# power.net
KiCad netlist of a schematic drawn in Altium Designer
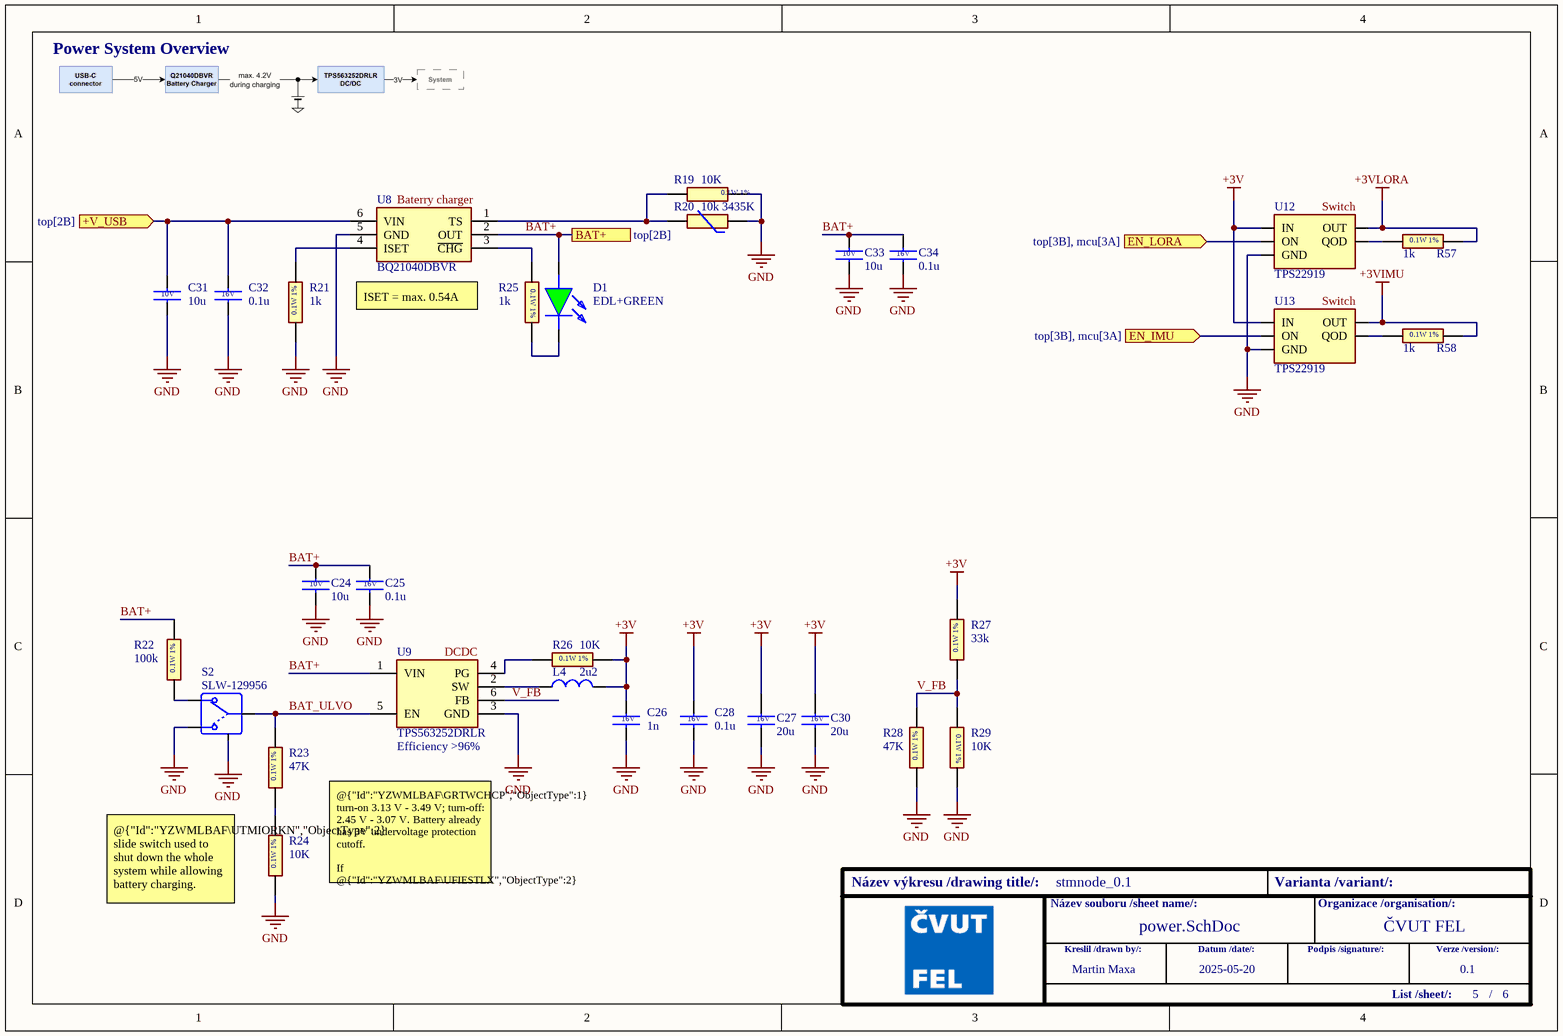
[diagram p0: power.SchDoc]

(export (version "E")
  (design (tool "Eeschema 10.0.6"))
  (components
    (comp (ref "C24")
      (value "10u")
      (footprint "C0603")
      (description "10 VDC, 20 %, X5R")
      (fields
        (field (name "MANUFACTURER_PART_NUMBER") "C0603C106M8PACTU")
        (field (name "MOUSER PART NUMBER") "80-C0603C106M8PACTU")
      )
      (libsource (lib "bch-lib") (part "ECK+10u10V"))
    )
    (comp (ref "C25")
      (value "0.1u")
      (footprint "CAPC1608X95N")
      (description "16V 0.1uF XR7 0603 10%")
      (fields
        (field (name "MANUFACTURER_PART_NUMBER") "C0603C104K4RAC-TU")
        (field (name "MOUSER PART NUMBER") "80-C0603C104K4RAC")
      )
      (libsource (lib "bch-lib") (part "ECK+100n16V"))
    )
    (comp (ref "C26")
      (value "1n")
      (footprint "CAPC1608X87N")
      (description "16 VDC, 10 %, X7R")
      (fields (field (name "MANUFACTURER_PART_NUMBER") "C0603C102K4RECTU"))
      (libsource (lib "bch-lib") (part "ECK+1n16V"))
    )
    (comp (ref "C27")
      (value "20u")
      (footprint "C0603")
      (description "Capacitor")
      (fields
        (field (name "MANUFACTURER_PART_NUMBER") "C0603C200K4HACAUTO")
        (field (name "MOUSER PART NUMBER") "80-C0603C200K4HAUTO")
      )
      (libsource (lib "bch-lib") (part "ECK+20u16V"))
    )
    (comp (ref "C28")
      (value "0.1u")
      (footprint "CAPC1608X95N")
      (description "16V 0.1uF XR7 0603 10%")
      (fields
        (field (name "MANUFACTURER_PART_NUMBER") "C0603C104K4RAC-TU")
        (field (name "MOUSER PART NUMBER") "80-C0603C104K4RAC")
      )
      (libsource (lib "bch-lib") (part "ECK+100n16V"))
    )
    (comp (ref "C30")
      (value "20u")
      (footprint "C0603")
      (description "Capacitor")
      (fields
        (field (name "MANUFACTURER_PART_NUMBER") "C0603C200K4HACAUTO")
        (field (name "MOUSER PART NUMBER") "80-C0603C200K4HAUTO")
      )
      (libsource (lib "bch-lib") (part "ECK+20u16V"))
    )
    (comp (ref "C31")
      (value "10u")
      (footprint "C0603")
      (description "10 VDC, 20 %, X5R")
      (fields
        (field (name "MANUFACTURER_PART_NUMBER") "C0603C106M8PACTU")
        (field (name "MOUSER PART NUMBER") "80-C0603C106M8PACTU")
      )
      (libsource (lib "bch-lib") (part "ECK+10u10V"))
    )
    (comp (ref "C32")
      (value "0.1u")
      (footprint "CAPC1608X95N")
      (description "16V 0.1uF XR7 0603 10%")
      (fields
        (field (name "MANUFACTURER_PART_NUMBER") "C0603C104K4RAC-TU")
        (field (name "MOUSER PART NUMBER") "80-C0603C104K4RAC")
      )
      (libsource (lib "bch-lib") (part "ECK+100n16V"))
    )
    (comp (ref "C33")
      (value "10u")
      (footprint "C0603")
      (description "10 VDC, 20 %, X5R")
      (fields
        (field (name "MANUFACTURER_PART_NUMBER") "C0603C106M8PACTU")
        (field (name "MOUSER PART NUMBER") "80-C0603C106M8PACTU")
      )
      (libsource (lib "bch-lib") (part "ECK+10u10V"))
    )
    (comp (ref "C34")
      (value "0.1u")
      (footprint "CAPC1608X95N")
      (description "16V 0.1uF XR7 0603 10%")
      (fields
        (field (name "MANUFACTURER_PART_NUMBER") "C0603C104K4RAC-TU")
        (field (name "MOUSER PART NUMBER") "80-C0603C104K4RAC")
      )
      (libsource (lib "bch-lib") (part "ECK+100n16V"))
    )
    (comp (ref "D1")
      (value "EDL+GREEN")
      (footprint "LEDM2012X80N")
      (description "LED GREEN,  3.2 V")
      (fields
        (field (name "MANUFACTURER_PART_NUMBER") "150080GS75000")
        (field (name "MOUSER PART NUMBER") "710-150080GS75000")
      )
      (libsource (lib "bch-lib") (part "EDL+GREEN"))
    )
    (comp (ref "L4")
      (value "2u2")
      (footprint "INDPM5752X300N")
      (description "Power Inductors - SMD 2.2uH 20%")
      (fields
        (field (name "MANUFACTURER_PART_NUMBER") "SRP5030TA-2R2M")
        (field (name "MOUSER PART NUMBER") "652-SRP5030TA-2R2M")
      )
      (libsource (lib "bch-lib") (part "EL+2.2u5.5A"))
    )
    (comp (ref "R19")
      (value "10K")
      (footprint "RESC1608X50N")
      (description "Resistor 1%, 0.1W")
      (fields
        (field (name "MANUFACTURER_PART_NUMBER") "CRCW060310K0FKEA")
        (field (name "MOUSER PART NUMBER") "71-CRCW0603-10K-E3")
      )
      (libsource (lib "") (part "ER+10K_1"))
    )
    (comp (ref "R20")
      (value "10k 3435K")
      (footprint "THRMC1608X90N")
      (description "NTC (Negative Temperature Coefficient) Thermistors NTC,10K,1%,0603,125C,AEC-Q200,ECO")
      (fields
        (field (name "MANUFACTURER_PART_NUMBER") "NTCGS163JF103FT7")
        (field (name "MOUSER PART NUMBER") "810-NTCGS163JF103FT7")
      )
      (libsource (lib "bch-lib") (part "ER+10kNTC3435K"))
    )
    (comp (ref "R21")
      (value "1k")
      (footprint "RESC1608X50N")
      (description "Resistor 1%, 0.1W")
      (fields
        (field (name "MANUFACTURER_PART_NUMBER") "CRCW06031K00FKEA")
        (field (name "MOUSER PART NUMBER") "71-CRCW0603-1.0K-E3")
      )
      (libsource (lib "") (part "ER+1K_1"))
    )
    (comp (ref "R22")
      (value "100k")
      (footprint "RESC1608X55N")
      (description "Thick Film Resistors 0603 - SMD 1/10Watt 100Kohms 1% Commercial Use")
      (fields
        (field (name "MANUFACTURER_PART_NUMBER") "AC0603FR-10100KL")
        (field (name "MOUSER PART NUMBER") "603-AC0603FR-10100KL")
      )
      (libsource (lib "bch-lib") (part "ER+100k"))
    )
    (comp (ref "R23")
      (value "47K")
      (footprint "RESC1608X50N")
      (description "Resistor 1%, 0.1W")
      (fields
        (field (name "MANUFACTURER_PART_NUMBER") "CRCW060347K0FKEA")
        (field (name "MOUSER PART NUMBER") "71-CRCW0603-47K-E3")
      )
      (libsource (lib "bch-lib") (part "ER+47K"))
    )
    (comp (ref "R24")
      (value "10K")
      (footprint "RESC1608X50N")
      (description "Resistor 1%, 0.1W")
      (fields
        (field (name "MANUFACTURER_PART_NUMBER") "CRCW060310K0FKEA")
        (field (name "MOUSER PART NUMBER") "71-CRCW0603-10K-E3")
      )
      (libsource (lib "") (part "ER+10K_2"))
    )
    (comp (ref "R25")
      (value "1k")
      (footprint "RESC1608X50N")
      (description "Resistor 1%, 0.1W")
      (fields
        (field (name "MANUFACTURER_PART_NUMBER") "CRCW06031K00FKEA")
        (field (name "MOUSER PART NUMBER") "71-CRCW0603-1.0K-E3")
      )
      (libsource (lib "") (part "ER+1K_2"))
    )
    (comp (ref "R26")
      (value "10K")
      (footprint "RESC1608X50N")
      (description "Resistor 1%, 0.1W")
      (fields
        (field (name "MANUFACTURER_PART_NUMBER") "CRCW060310K0FKEA")
        (field (name "MOUSER PART NUMBER") "71-CRCW0603-10K-E3")
      )
      (libsource (lib "bch-lib") (part "ER+10K"))
    )
    (comp (ref "R27")
      (value "33k")
      (footprint "RESC1608X55N")
      (description "Thick Film Resistors - SMD General Purpose Chip Resistor 0603, 33kOhms, 1%, 1/10W")
      (fields
        (field (name "MANUFACTURER_PART_NUMBER") "RC0603FR-1333KL")
        (field (name "MOUSER PART NUMBER") "603-RC0603FR-1333KL")
      )
      (libsource (lib "bch-lib") (part "ER+33k"))
    )
    (comp (ref "R28")
      (value "47K")
      (footprint "RESC1608X50N")
      (description "Resistor 1%, 0.1W")
      (fields
        (field (name "MANUFACTURER_PART_NUMBER") "CRCW060347K0FKEA")
        (field (name "MOUSER PART NUMBER") "71-CRCW0603-47K-E3")
      )
      (libsource (lib "bch-lib") (part "ER+47K"))
    )
    (comp (ref "R29")
      (value "10K")
      (footprint "RESC1608X50N")
      (description "Resistor 1%, 0.1W")
      (fields
        (field (name "MANUFACTURER_PART_NUMBER") "CRCW060310K0FKEA")
        (field (name "MOUSER PART NUMBER") "71-CRCW0603-10K-E3")
      )
      (libsource (lib "") (part "ER+10K_1"))
    )
    (comp (ref "R57")
      (value "1k")
      (footprint "RESC1608X50N")
      (description "Resistor 1%, 0.1W")
      (fields
        (field (name "MANUFACTURER_PART_NUMBER") "CRCW06031K00FKEA")
        (field (name "MOUSER PART NUMBER") "71-CRCW0603-1.0K-E3")
      )
      (libsource (lib "bch-lib") (part "ER+1K"))
    )
    (comp (ref "R58")
      (value "1k")
      (footprint "RESC1608X50N")
      (description "Resistor 1%, 0.1W")
      (fields
        (field (name "MANUFACTURER_PART_NUMBER") "CRCW06031K00FKEA")
        (field (name "MOUSER PART NUMBER") "71-CRCW0603-1.0K-E3")
      )
      (libsource (lib "bch-lib") (part "ER+1K"))
    )
    (comp (ref "S2")
      (value "SLW-129956")
      (footprint "SLW1299564ARAND")
      (description "Slide Switch, Right Angle, max. 50 VDC, max. 300 mA, ON - ON")
      (fields
        (field (name "MANUFACTURER_PART_NUMBER") "SLW-129956-4A-RA-N-D")
        (field (name "MOUSER PART NUMBER") "179-SLW1299564ARAND")
      )
      (libsource (lib "bch-lib") (part "ESW-SLW-129956"))
    )
    (comp (ref "U8")
      (value "BQ21040DBVR")
      (footprint "SOT95P280X145-6N")
      (description "Battery Management 1-cell 0.8-A Li-ion and Li-polymer batt A 595-BQ21040DBVT")
      (fields (field (name "MOUSER PART NUMBER") "595-BQ21040DBVR"))
      (libsource (lib "bch-lib") (part "EU+BQ21040DBVR"))
    )
    (comp (ref "U9")
      (value "TPS563252DRLR")
      (footprint "SOTFL50P160X60-6N")
      (description "Switching Voltage Regulators 3-V to 17-V input vo ltage 3-A 1.2-Mhz")
      (fields (field (name "MOUSER PART NUMBER") "595-TPS563252DRLR"))
      (libsource (lib "bch-lib") (part "EU+TPS563252DRLR"))
    )
    (comp (ref "U12")
      (value "TPS22919")
      (footprint "SOT65P210X110-6N")
      (description "Power Switch ICs - Power Distribution 1-ch 5.5V 1.5A 90 mOhm self-protected AE")
      (fields
        (field (name "MANUFACTURER_PART_NUMBER") "TPS22919QDCKRQ1")
        (field (name "MOUSER PART NUMBER") "595-TPS22919QDCKRQ1")
      )
      (libsource (lib "bch-lib") (part "EU+TPS22919"))
    )
    (comp (ref "U13")
      (value "TPS22919")
      (footprint "SOT65P210X110-6N")
      (description "Power Switch ICs - Power Distribution 1-ch 5.5V 1.5A 90 mOhm self-protected AE")
      (fields
        (field (name "MANUFACTURER_PART_NUMBER") "TPS22919QDCKRQ1")
        (field (name "MOUSER PART NUMBER") "595-TPS22919QDCKRQ1")
      )
      (libsource (lib "bch-lib") (part "EU+TPS22919"))
    )
  )
  (nets
    (net (code "1") (name "+3V") (class "Default")
      (node (ref "C26") (pin "1") (pinfunction "1_1") (pintype "passive"))
      (node (ref "C27") (pin "1") (pinfunction "1_1") (pintype "passive"))
      (node (ref "C28") (pin "1") (pinfunction "1_1") (pintype "passive"))
      (node (ref "C30") (pin "1") (pinfunction "1_1") (pintype "passive"))
      (node (ref "L4") (pin "24") (pinfunction "24_24") (pintype "passive"))
      (node (ref "R26") (pin "2") (pinfunction "2_2") (pintype "passive"))
      (node (ref "R27") (pin "2") (pinfunction "2_2") (pintype "passive"))
      (node (ref "U12") (pin "1") (pinfunction "IN_1") (pintype "passive"))
      (node (ref "U13") (pin "1") (pinfunction "IN_1") (pintype "passive"))
    )
    (net (code "2") (name "+3VIMU") (class "Default")
      (node (ref "R58") (pin "2") (pinfunction "2_2") (pintype "passive"))
      (node (ref "U13") (pin "6") (pinfunction "OUT_6") (pintype "passive"))
    )
    (net (code "3") (name "+3VLORA") (class "Default")
      (node (ref "R57") (pin "2") (pinfunction "2_2") (pintype "passive"))
      (node (ref "U12") (pin "6") (pinfunction "OUT_6") (pintype "passive"))
    )
    (net (code "4") (name "/+V_USB") (class "Default")
      (node (ref "C31") (pin "1") (pinfunction "1_1") (pintype "passive"))
      (node (ref "C32") (pin "1") (pinfunction "1_1") (pintype "passive"))
      (node (ref "U8") (pin "6") (pinfunction "VIN_6") (pintype "passive"))
    )
    (net (code "5") (name "/BAT+") (class "Default")
      (node (ref "C24") (pin "1") (pinfunction "1_1") (pintype "passive"))
      (node (ref "C25") (pin "1") (pinfunction "1_1") (pintype "passive"))
      (node (ref "C33") (pin "1") (pinfunction "1_1") (pintype "passive"))
      (node (ref "C34") (pin "1") (pinfunction "1_1") (pintype "passive"))
      (node (ref "D1") (pin "1") (pinfunction "K_1") (pintype "passive"))
      (node (ref "R22") (pin "2") (pinfunction "2_2") (pintype "passive"))
      (node (ref "U8") (pin "2") (pinfunction "OUT_2") (pintype "passive"))
      (node (ref "U9") (pin "1") (pinfunction "VIN_1") (pintype "passive"))
    )
    (net (code "6") (name "/BAT_ULVO") (class "Default")
      (node (ref "R23") (pin "2") (pinfunction "2_2") (pintype "passive"))
      (node (ref "S2") (pin "2") (pinfunction "COM_2") (pintype "passive"))
      (node (ref "U9") (pin "5") (pinfunction "EN_5") (pintype "passive"))
    )
    (net (code "7") (name "/EN_IMU") (class "Default")
      (node (ref "U13") (pin "3") (pinfunction "ON_3") (pintype "passive"))
    )
    (net (code "8") (name "/EN_LORA") (class "Default")
      (node (ref "U12") (pin "3") (pinfunction "ON_3") (pintype "passive"))
    )
    (net (code "9") (name "/V_FB") (class "Default")
      (node (ref "R27") (pin "1") (pinfunction "1_1") (pintype "passive"))
      (node (ref "R28") (pin "2") (pinfunction "2_2") (pintype "passive"))
      (node (ref "R29") (pin "1") (pinfunction "1_1") (pintype "passive"))
      (node (ref "U9") (pin "6") (pinfunction "FB_6") (pintype "passive"))
    )
    (net (code "10") (name "GND") (class "Default")
      (node (ref "C24") (pin "2") (pinfunction "2_2") (pintype "passive"))
      (node (ref "C25") (pin "2") (pinfunction "2_2") (pintype "passive"))
      (node (ref "C26") (pin "2") (pinfunction "2_2") (pintype "passive"))
      (node (ref "C27") (pin "2") (pinfunction "2_2") (pintype "passive"))
      (node (ref "C28") (pin "2") (pinfunction "2_2") (pintype "passive"))
      (node (ref "C30") (pin "2") (pinfunction "2_2") (pintype "passive"))
      (node (ref "C31") (pin "2") (pinfunction "2_2") (pintype "passive"))
      (node (ref "C32") (pin "2") (pinfunction "2_2") (pintype "passive"))
      (node (ref "C33") (pin "2") (pinfunction "2_2") (pintype "passive"))
      (node (ref "C34") (pin "2") (pinfunction "2_2") (pintype "passive"))
      (node (ref "R19") (pin "1") (pinfunction "1_1") (pintype "passive"))
      (node (ref "R20") (pin "1") (pinfunction "1_1") (pintype "passive"))
      (node (ref "R21") (pin "1") (pinfunction "1_1") (pintype "passive"))
      (node (ref "R24") (pin "1") (pinfunction "1_1") (pintype "passive"))
      (node (ref "R28") (pin "1") (pinfunction "1_1") (pintype "passive"))
      (node (ref "R29") (pin "2") (pinfunction "2_2") (pintype "passive"))
      (node (ref "S2") (pin "3") (pinfunction "NO_3") (pintype "passive"))
      (node (ref "S2") (pin "4") (pinfunction "MH1_4") (pintype "passive"))
      (node (ref "U12") (pin "2") (pinfunction "GND_2") (pintype "passive"))
      (node (ref "U13") (pin "2") (pinfunction "GND_2") (pintype "passive"))
      (node (ref "U8") (pin "5") (pinfunction "GND_5") (pintype "power_in"))
      (node (ref "U9") (pin "3") (pinfunction "GND_3") (pintype "passive"))
    )
    (net (code "11") (name "Net-(D1-A)") (class "Default")
      (node (ref "D1") (pin "2") (pinfunction "A_2") (pintype "passive"))
      (node (ref "R25") (pin "2") (pinfunction "2_2") (pintype "passive"))
    )
    (net (code "12") (name "Net-(R22-Pad1)") (class "Default")
      (node (ref "R22") (pin "1") (pinfunction "1_1") (pintype "passive"))
      (node (ref "S2") (pin "1") (pinfunction "NO_1") (pintype "passive"))
    )
    (net (code "13") (name "Net-(R23-Pad1)") (class "Default")
      (node (ref "R23") (pin "1") (pinfunction "1_1") (pintype "passive"))
      (node (ref "R24") (pin "2") (pinfunction "2_2") (pintype "passive"))
    )
    (net (code "14") (name "Net-(U8-ISET)") (class "Default")
      (node (ref "R21") (pin "2") (pinfunction "2_2") (pintype "passive"))
      (node (ref "U8") (pin "4") (pinfunction "ISET_4") (pintype "passive"))
    )
    (net (code "15") (name "Net-(U8-TS)") (class "Default")
      (node (ref "R19") (pin "2") (pinfunction "2_2") (pintype "passive"))
      (node (ref "R20") (pin "2") (pinfunction "2_2") (pintype "passive"))
      (node (ref "U8") (pin "1") (pinfunction "TS_1") (pintype "passive"))
    )
    (net (code "16") (name "Net-(U8-~{CHG})") (class "Default")
      (node (ref "R25") (pin "1") (pinfunction "1_1") (pintype "passive"))
      (node (ref "U8") (pin "3") (pinfunction "~{CHG}_3") (pintype "passive"))
    )
    (net (code "17") (name "Net-(U9-PG)") (class "Default")
      (node (ref "R26") (pin "1") (pinfunction "1_1") (pintype "passive"))
      (node (ref "U9") (pin "4") (pinfunction "PG_4") (pintype "passive"))
    )
    (net (code "18") (name "Net-(U9-SW)") (class "Default")
      (node (ref "L4") (pin "23") (pinfunction "23_23") (pintype "passive"))
      (node (ref "U9") (pin "2") (pinfunction "SW_2") (pintype "passive"))
    )
    (net (code "19") (name "Net-(U12-QOD)") (class "Default")
      (node (ref "R57") (pin "1") (pinfunction "1_1") (pintype "passive"))
      (node (ref "U12") (pin "5") (pinfunction "QOD_5") (pintype "passive"))
    )
    (net (code "20") (name "Net-(U13-QOD)") (class "Default")
      (node (ref "R58") (pin "1") (pinfunction "1_1") (pintype "passive"))
      (node (ref "U13") (pin "5") (pinfunction "QOD_5") (pintype "passive"))
    )
  )
)
